# algyan-6th-03.net
KiCad netlist of a schematic drawn in EAGLE
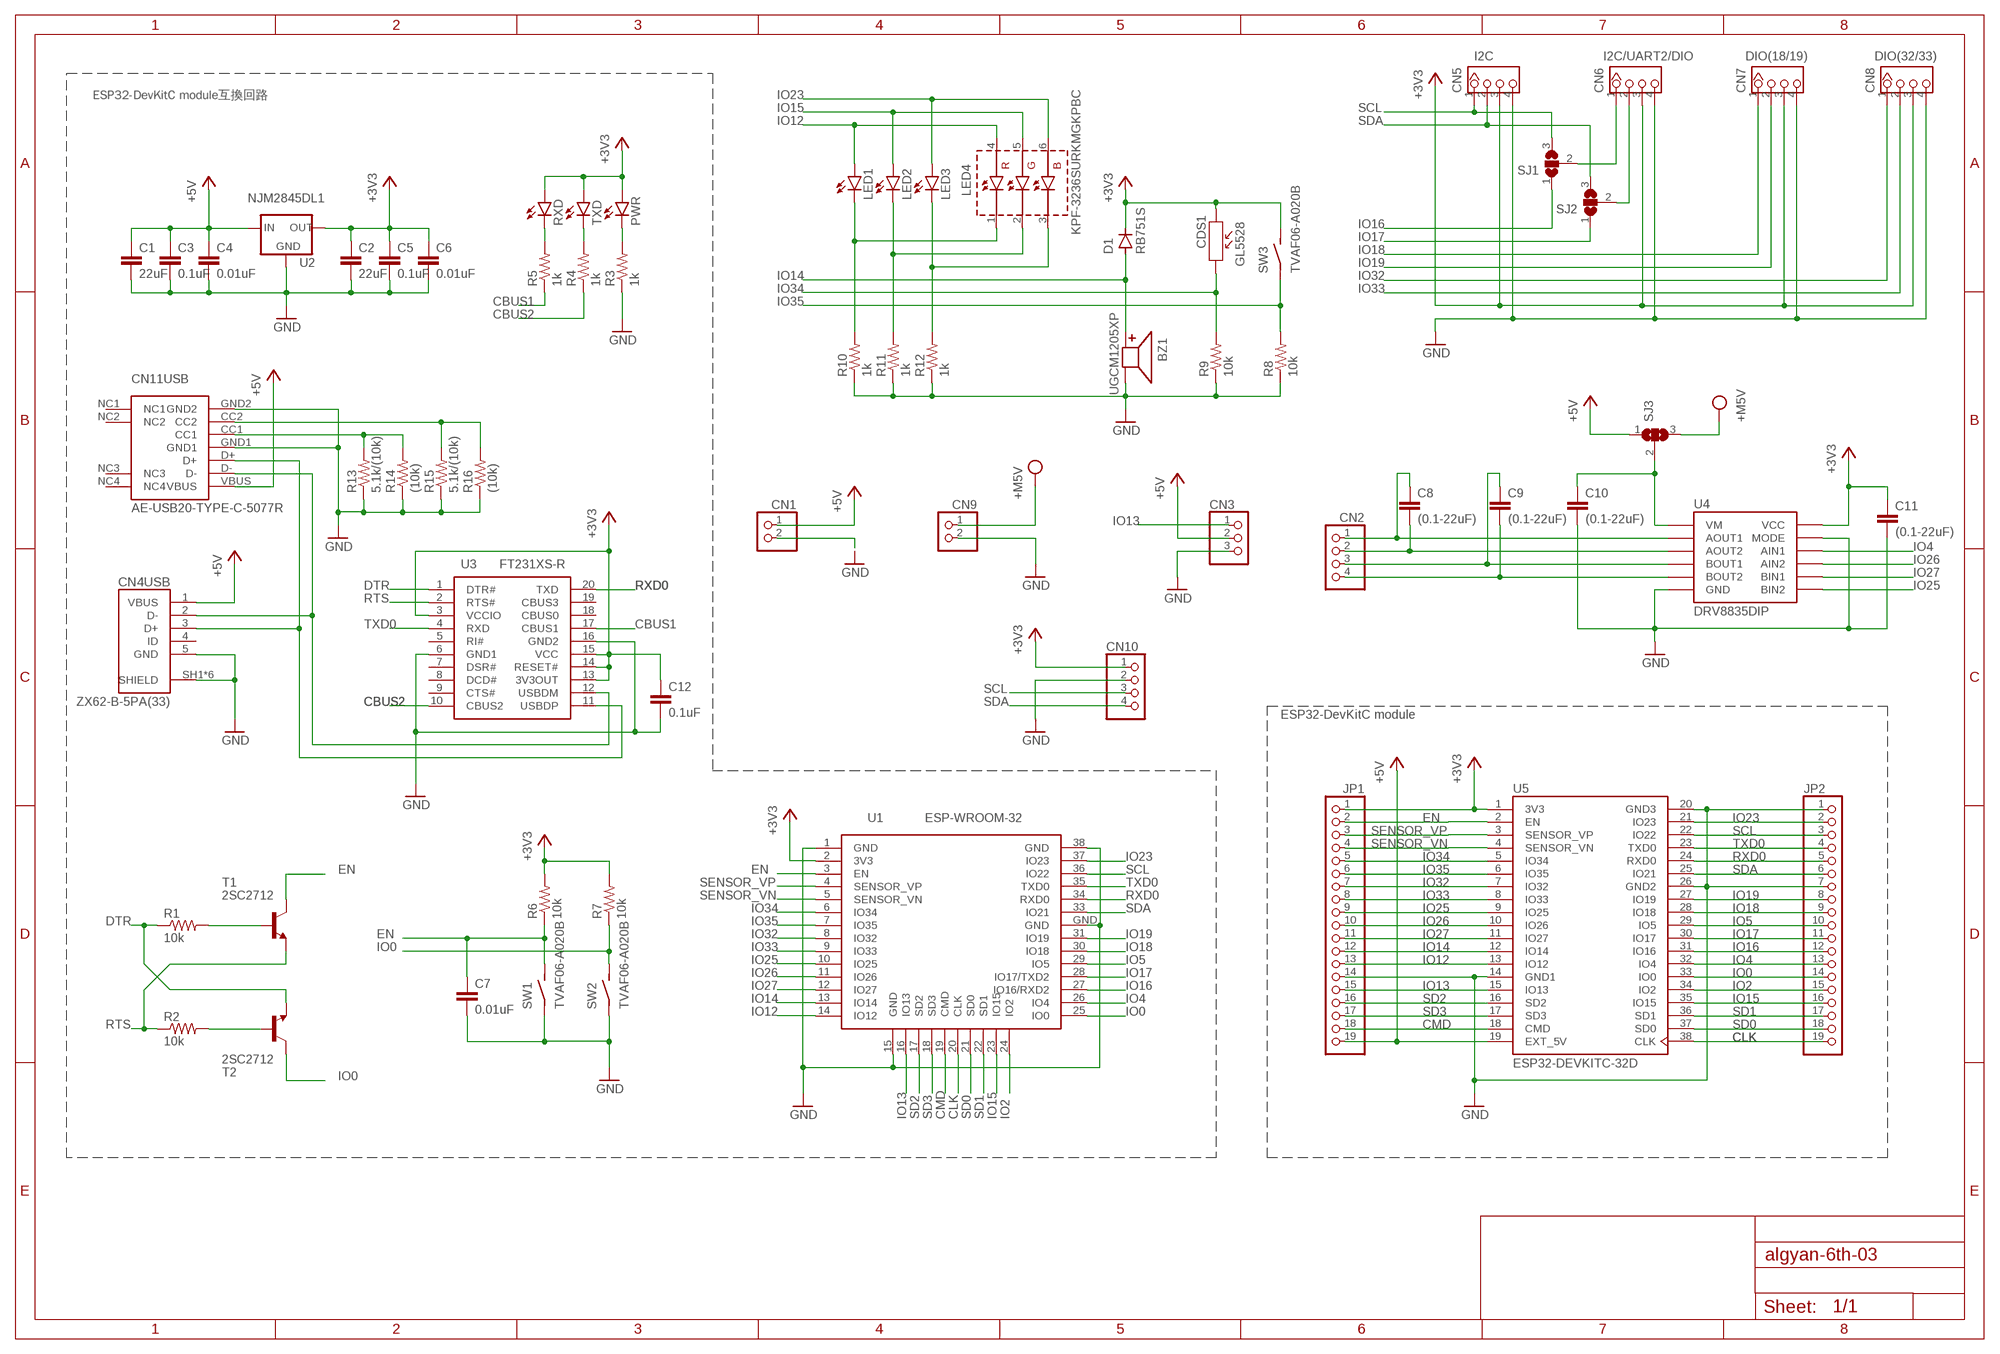
[diagram p0: schematic, sheet 1]

(export (version "E")
  (design (tool "Eeschema 10.0.6"))
  (components
    (comp (ref "BZ1")
      (value "UGCM1205XP")
      (footprint "eagle-import:UGCM1205XP")
      (libsource (lib "eagle-import") (part "UGCM1205XP"))
    )
    (comp (ref "C1")
      (value "22uF")
      (footprint "eagle-import:C3216")
      (libsource (lib "eagle-import") (part "C-EUC3216"))
    )
    (comp (ref "C2")
      (value "22uF")
      (footprint "eagle-import:C3216")
      (libsource (lib "eagle-import") (part "C-EUC3216"))
    )
    (comp (ref "C3")
      (value "0.1uF")
      (footprint "eagle-import:C2012")
      (libsource (lib "eagle-import") (part "C-EUC2012"))
    )
    (comp (ref "C4")
      (value "0.01uF")
      (footprint "eagle-import:C1608")
      (libsource (lib "eagle-import") (part "C-EUC1608"))
    )
    (comp (ref "C5")
      (value "0.1uF")
      (footprint "eagle-import:C2012")
      (libsource (lib "eagle-import") (part "C-EUC2012"))
    )
    (comp (ref "C6")
      (value "0.01uF")
      (footprint "eagle-import:C1608")
      (libsource (lib "eagle-import") (part "C-EUC1608"))
    )
    (comp (ref "C7")
      (value "0.01uF")
      (footprint "eagle-import:C1608")
      (libsource (lib "eagle-import") (part "C-EUC1608"))
    )
    (comp (ref "C8")
      (value "(0.1-22uF)")
      (footprint "eagle-import:C3216")
      (libsource (lib "eagle-import") (part "C-EUC3216"))
    )
    (comp (ref "C9")
      (value "(0.1-22uF)")
      (footprint "eagle-import:C3216")
      (libsource (lib "eagle-import") (part "C-EUC3216"))
    )
    (comp (ref "C10")
      (value "(0.1-22uF)")
      (footprint "eagle-import:C3216")
      (libsource (lib "eagle-import") (part "C-EUC3216"))
    )
    (comp (ref "C11")
      (value "(0.1-22uF)")
      (footprint "eagle-import:C3216")
      (libsource (lib "eagle-import") (part "C-EUC3216"))
    )
    (comp (ref "C12")
      (value "0.1uF")
      (footprint "eagle-import:C2012")
      (libsource (lib "eagle-import") (part "C-EUC2012"))
    )
    (comp (ref "CDS1")
      (value "GL5528")
      (footprint "eagle-import:GL5528")
      (libsource (lib "eagle-import") (part "GL5528"))
    )
    (comp (ref "CN1")
      (value "PINHD-1X2")
      (footprint "eagle-import:1X02")
      (libsource (lib "eagle-import") (part "PINHD-1X2"))
    )
    (comp (ref "CN2")
      (value "PINHD-1X4")
      (footprint "eagle-import:1X04")
      (libsource (lib "eagle-import") (part "PINHD-1X4"))
    )
    (comp (ref "CN3")
      (value "PINHD-1X3")
      (footprint "eagle-import:1X03")
      (libsource (lib "eagle-import") (part "PINHD-1X3"))
    )
    (comp (ref "CN4USB")
      (value "ZX62-B-5PA(33)")
      (footprint "eagle-import:HRS_ZX62-B-5PA(33)")
      (fields (field (name "MF") "Hirose"))
      (libsource (lib "eagle-import") (part "ZX62-B-5PA(33)"))
    )
    (comp (ref "CN5")
      (value "I2C")
      (footprint "eagle-import:HW4-2.0")
      (fields (field (name "CN5") "I2C"))
      (libsource (lib "eagle-import") (part "GROVE-CONNECTOR-DIP(4P-2.0)"))
    )
    (comp (ref "CN6")
      (value "I2C/UART2")
      (footprint "eagle-import:HW4-2.0")
      (fields (field (name "CN6") "I2C/UART2/DIO"))
      (libsource (lib "eagle-import") (part "GROVE-CONNECTOR-DIP(4P-2.0)"))
    )
    (comp (ref "CN7")
      (value "DIO(18/19)")
      (footprint "eagle-import:HW4-2.0")
      (fields (field (name "CN7") "DIO(18/19)"))
      (libsource (lib "eagle-import") (part "GROVE-CONNECTOR-DIP(4P-2.0)"))
    )
    (comp (ref "CN8")
      (value "DIO(32/33)")
      (footprint "eagle-import:HW4-2.0")
      (fields (field (name "CN8") "DIO(32/33)"))
      (libsource (lib "eagle-import") (part "GROVE-CONNECTOR-DIP(4P-2.0)"))
    )
    (comp (ref "CN9")
      (value "PINHD-1X2")
      (footprint "eagle-import:1X02")
      (libsource (lib "eagle-import") (part "PINHD-1X2"))
    )
    (comp (ref "CN10")
      (value "PINHD-1X4/90")
      (footprint "eagle-import:1X04_90")
      (libsource (lib "eagle-import") (part "PINHD-1X4/90"))
    )
    (comp (ref "CN11USB")
      (value "AE-USB20-TYPE-C-5077R")
      (footprint "eagle-import:AE-USB20-TYPE-C-5077R")
      (libsource (lib "eagle-import") (part "AE-USB20-TYPE-C-5077R"))
    )
    (comp (ref "D1")
      (value "RB751S")
      (footprint "eagle-import:SOD-523")
      (libsource (lib "eagle-import") (part "RB751S"))
    )
    (comp (ref "JP1")
      (value "PINHD-1X19")
      (footprint "eagle-import:1X19")
      (libsource (lib "eagle-import") (part "PINHD-1X19"))
    )
    (comp (ref "JP2")
      (value "PINHD-1X19")
      (footprint "eagle-import:1X19")
      (libsource (lib "eagle-import") (part "PINHD-1X19"))
    )
    (comp (ref "LED1")
      (value "LEDCHIPLED_0805")
      (footprint "eagle-import:CHIPLED_0805")
      (libsource (lib "eagle-import") (part "LEDCHIPLED_0805"))
    )
    (comp (ref "LED2")
      (value "LEDCHIPLED_0805")
      (footprint "eagle-import:CHIPLED_0805")
      (libsource (lib "eagle-import") (part "LEDCHIPLED_0805"))
    )
    (comp (ref "LED3")
      (value "LEDCHIPLED_0805")
      (footprint "eagle-import:CHIPLED_0805")
      (libsource (lib "eagle-import") (part "LEDCHIPLED_0805"))
    )
    (comp (ref "LED4")
      (value "KPF-3236SURKMGKPBC")
      (footprint "eagle-import:KPF-3236SURKMGKPBC")
      (libsource (lib "eagle-import") (part "KPF-3236SURKMGKPBC"))
    )
    (comp (ref "PWR")
      (value "LEDCHIPLED_0805")
      (footprint "eagle-import:CHIPLED_0805")
      (libsource (lib "eagle-import") (part "LEDCHIPLED_0805"))
    )
    (comp (ref "R1")
      (value "10k")
      (footprint "eagle-import:R2012")
      (libsource (lib "eagle-import") (part "resistor_348_R-US_R2012"))
    )
    (comp (ref "R2")
      (value "10k")
      (footprint "eagle-import:R2012")
      (libsource (lib "eagle-import") (part "resistor_348_R-US_R2012"))
    )
    (comp (ref "R3")
      (value "1k")
      (footprint "eagle-import:R2012")
      (libsource (lib "eagle-import") (part "R-US_R2012"))
    )
    (comp (ref "R4")
      (value "1k")
      (footprint "eagle-import:R2012")
      (libsource (lib "eagle-import") (part "R-US_R2012"))
    )
    (comp (ref "R5")
      (value "1k")
      (footprint "eagle-import:R2012")
      (libsource (lib "eagle-import") (part "R-US_R2012"))
    )
    (comp (ref "R6")
      (value "10k")
      (footprint "eagle-import:R2012")
      (libsource (lib "eagle-import") (part "resistor_348_R-US_R2012"))
    )
    (comp (ref "R7")
      (value "10k")
      (footprint "eagle-import:R2012")
      (libsource (lib "eagle-import") (part "resistor_348_R-US_R2012"))
    )
    (comp (ref "R8")
      (value "10k")
      (footprint "eagle-import:R2012")
      (libsource (lib "eagle-import") (part "resistor_348_R-US_R2012"))
    )
    (comp (ref "R9")
      (value "10k")
      (footprint "eagle-import:R2012")
      (libsource (lib "eagle-import") (part "resistor_348_R-US_R2012"))
    )
    (comp (ref "R10")
      (value "1k")
      (footprint "eagle-import:R2012")
      (libsource (lib "eagle-import") (part "R-US_R2012"))
    )
    (comp (ref "R11")
      (value "1k")
      (footprint "eagle-import:R2012")
      (libsource (lib "eagle-import") (part "R-US_R2012"))
    )
    (comp (ref "R12")
      (value "1k")
      (footprint "eagle-import:R2012")
      (libsource (lib "eagle-import") (part "R-US_R2012"))
    )
    (comp (ref "R13")
      (value "5.1k/(10k)")
      (footprint "eagle-import:R2012")
      (libsource (lib "eagle-import") (part "resistor_348_R-US_R2012"))
    )
    (comp (ref "R14")
      (value "(10k)")
      (footprint "eagle-import:R2012")
      (libsource (lib "eagle-import") (part "resistor_348_R-US_R2012"))
    )
    (comp (ref "R15")
      (value "5.1k/(10k)")
      (footprint "eagle-import:R2012")
      (libsource (lib "eagle-import") (part "resistor_348_R-US_R2012"))
    )
    (comp (ref "R16")
      (value "(10k)")
      (footprint "eagle-import:R2012")
      (libsource (lib "eagle-import") (part "resistor_348_R-US_R2012"))
    )
    (comp (ref "RXD")
      (value "LEDCHIPLED_0805")
      (footprint "eagle-import:CHIPLED_0805")
      (libsource (lib "eagle-import") (part "LEDCHIPLED_0805"))
    )
    (comp (ref "SJ1")
      (value "SJ2W")
      (footprint "eagle-import:SJ_2")
      (libsource (lib "eagle-import") (part "SJ2W"))
    )
    (comp (ref "SJ2")
      (value "SJ2W")
      (footprint "eagle-import:SJ_2")
      (libsource (lib "eagle-import") (part "SJ2W"))
    )
    (comp (ref "SJ3")
      (value "SJ2W")
      (footprint "eagle-import:SJ_2")
      (libsource (lib "eagle-import") (part "SJ2W"))
    )
    (comp (ref "SW1")
      (value "TVAF06-A020B")
      (footprint "eagle-import:TVAF06-A020B")
      (libsource (lib "eagle-import") (part "TVAF06-A020B"))
    )
    (comp (ref "SW2")
      (value "TVAF06-A020B")
      (footprint "eagle-import:TVAF06-A020B")
      (libsource (lib "eagle-import") (part "TVAF06-A020B"))
    )
    (comp (ref "SW3")
      (value "TVAF06-A020B")
      (footprint "eagle-import:TVAF06-A020B")
      (libsource (lib "eagle-import") (part "TVAF06-A020B"))
    )
    (comp (ref "T1")
      (value "2SC2712")
      (footprint "eagle-import:SOT23-BEC")
      (libsource (lib "eagle-import") (part "2SC2712YSOT23-BECBC808"))
    )
    (comp (ref "T2")
      (value "2SC2712")
      (footprint "eagle-import:SOT23-BEC")
      (libsource (lib "eagle-import") (part "2SC2712YSOT23-BECBC808"))
    )
    (comp (ref "TXD")
      (value "LEDCHIPLED_0805")
      (footprint "eagle-import:CHIPLED_0805")
      (libsource (lib "eagle-import") (part "LEDCHIPLED_0805"))
    )
    (comp (ref "U1")
      (value "ESP-WROOM-32")
      (footprint "eagle-import:ESP-WROOM-32")
      (libsource (lib "eagle-import") (part "ESP-WROOM-32"))
    )
    (comp (ref "U2")
      (value "NJM2845DL1")
      (footprint "eagle-import:D-PAK_TO252AA")
      (libsource (lib "eagle-import") (part "NJM2845DL1"))
    )
    (comp (ref "U3")
      (value "FT231XS-R")
      (footprint "eagle-import:SOP64P599X175-20N")
      (fields (field (name "RS_PART_NUMBER") "7570032P"))
      (libsource (lib "eagle-import") (part "FT231XS-R"))
    )
    (comp (ref "U4")
      (value "DRV8835DIP")
      (footprint "eagle-import:DRV8835DIP")
      (libsource (lib "eagle-import") (part "DRV8835DIP"))
    )
    (comp (ref "U5")
      (value "ESP32-DEVKITC-32D")
      (footprint "eagle-import:MODULE_ESP32-DEVKITC-32D")
      (fields (field (name "MF") "Espressif Systems"))
      (libsource (lib "eagle-import") (part "ESP32-DEVKITC-32D"))
    )
  )
  (nets
    (net (code "1") (name "+3V3") (class "Default")
      (node (ref "C11") (pin "1") (pinfunction "1_1") (pintype "passive"))
      (node (ref "C12") (pin "1") (pinfunction "1_1") (pintype "passive"))
      (node (ref "C2") (pin "1") (pinfunction "1_1") (pintype "passive"))
      (node (ref "C5") (pin "1") (pinfunction "1_1") (pintype "passive"))
      (node (ref "C6") (pin "1") (pinfunction "1_1") (pintype "passive"))
      (node (ref "CDS1") (pin "1") (pinfunction "P$1_1") (pintype "bidirectional"))
      (node (ref "CN10") (pin "1") (pinfunction "1_1") (pintype "passive"))
      (node (ref "CN5") (pin "3") (pinfunction "3_3") (pintype "bidirectional"))
      (node (ref "CN6") (pin "3") (pinfunction "3_3") (pintype "bidirectional"))
      (node (ref "CN7") (pin "3") (pinfunction "3_3") (pintype "bidirectional"))
      (node (ref "CN8") (pin "3") (pinfunction "3_3") (pintype "bidirectional"))
      (node (ref "D1") (pin "C") (pinfunction "C_C") (pintype "passive"))
      (node (ref "JP1") (pin "1") (pinfunction "1_1") (pintype "passive"))
      (node (ref "PWR") (pin "A") (pinfunction "A_A") (pintype "passive"))
      (node (ref "R6") (pin "2") (pinfunction "2_2") (pintype "passive"))
      (node (ref "R7") (pin "2") (pinfunction "2_2") (pintype "passive"))
      (node (ref "RXD") (pin "A") (pinfunction "A_A") (pintype "passive"))
      (node (ref "SW3") (pin "2") (pinfunction "S_2") (pintype "passive"))
      (node (ref "TXD") (pin "A") (pinfunction "A_A") (pintype "passive"))
      (node (ref "U1") (pin "2") (pinfunction "3V3_2") (pintype "power_in"))
      (node (ref "U2") (pin "3") (pinfunction "OUT_3") (pintype "passive"))
      (node (ref "U3") (pin "13") (pinfunction "3V3OUT_13") (pintype "output"))
      (node (ref "U3") (pin "14") (pinfunction "RESET#_14") (pintype "bidirectional"))
      (node (ref "U3") (pin "15") (pinfunction "VCC_15") (pintype "power_in"))
      (node (ref "U3") (pin "3") (pinfunction "VCCIO_3") (pintype "power_in"))
      (node (ref "U4") (pin "VCC") (pinfunction "VCC_VCC") (pintype "bidirectional"))
      (node (ref "U5") (pin "1") (pinfunction "3V3_1") (pintype "power_in"))
    )
    (net (code "2") (name "+5V") (class "Default")
      (node (ref "C1") (pin "1") (pinfunction "1_1") (pintype "passive"))
      (node (ref "C3") (pin "1") (pinfunction "1_1") (pintype "passive"))
      (node (ref "C4") (pin "1") (pinfunction "1_1") (pintype "passive"))
      (node (ref "CN1") (pin "1") (pinfunction "1_1") (pintype "passive"))
      (node (ref "CN11USB") (pin "VBUS") (pinfunction "VBUS_VBUS") (pintype "bidirectional"))
      (node (ref "CN3") (pin "2") (pinfunction "2_2") (pintype "passive"))
      (node (ref "CN4USB") (pin "1") (pinfunction "VBUS_1") (pintype "passive"))
      (node (ref "JP1") (pin "19") (pinfunction "19_19") (pintype "passive"))
      (node (ref "SJ3") (pin "1") (pinfunction "1_1") (pintype "passive"))
      (node (ref "U2") (pin "1") (pinfunction "IN_1") (pintype "input"))
      (node (ref "U5") (pin "19") (pinfunction "EXT_5V_19") (pintype "power_in"))
    )
    (net (code "3") (name "+M5V") (class "Default")
      (node (ref "CN9") (pin "1") (pinfunction "1_1") (pintype "passive"))
      (node (ref "SJ3") (pin "3") (pinfunction "3_3") (pintype "passive"))
    )
    (net (code "4") (name "/CBUS1") (class "Default")
      (node (ref "R5") (pin "1") (pinfunction "1_1") (pintype "passive"))
      (node (ref "U3") (pin "17") (pinfunction "CBUS1_17") (pintype "bidirectional"))
    )
    (net (code "5") (name "/CBUS2") (class "Default")
      (node (ref "R4") (pin "1") (pinfunction "1_1") (pintype "passive"))
      (node (ref "U3") (pin "10") (pinfunction "CBUS2_10") (pintype "bidirectional"))
    )
    (net (code "6") (name "/CLK") (class "Default")
      (node (ref "JP2") (pin "19") (pinfunction "19_19") (pintype "passive"))
      (node (ref "U1") (pin "20") (pinfunction "CLK_20") (pintype "bidirectional"))
      (node (ref "U5") (pin "38") (pinfunction "CLK_38") (pintype "input"))
    )
    (net (code "7") (name "/CMD") (class "Default")
      (node (ref "JP1") (pin "18") (pinfunction "18_18") (pintype "passive"))
      (node (ref "U1") (pin "19") (pinfunction "CMD_19") (pintype "bidirectional"))
      (node (ref "U5") (pin "18") (pinfunction "CMD_18") (pintype "bidirectional"))
    )
    (net (code "8") (name "/DTR") (class "Default")
      (node (ref "R1") (pin "1") (pinfunction "1_1") (pintype "passive"))
      (node (ref "T2") (pin "E") (pinfunction "E_E") (pintype "passive"))
      (node (ref "U3") (pin "1") (pinfunction "DTR#_1") (pintype "bidirectional"))
    )
    (net (code "9") (name "/EN") (class "Default")
      (node (ref "C7") (pin "1") (pinfunction "1_1") (pintype "passive"))
      (node (ref "JP1") (pin "2") (pinfunction "2_2") (pintype "passive"))
      (node (ref "R6") (pin "1") (pinfunction "1_1") (pintype "passive"))
      (node (ref "SW1") (pin "2") (pinfunction "S_2") (pintype "passive"))
      (node (ref "T1") (pin "C") (pinfunction "C_C") (pintype "passive"))
      (node (ref "U1") (pin "3") (pinfunction "EN_3") (pintype "input"))
      (node (ref "U5") (pin "2") (pinfunction "EN_2") (pintype "input"))
    )
    (net (code "10") (name "/IO0") (class "Default")
      (node (ref "JP2") (pin "14") (pinfunction "14_14") (pintype "passive"))
      (node (ref "R7") (pin "1") (pinfunction "1_1") (pintype "passive"))
      (node (ref "SW2") (pin "2") (pinfunction "S_2") (pintype "passive"))
      (node (ref "T2") (pin "C") (pinfunction "C_C") (pintype "passive"))
      (node (ref "U1") (pin "25") (pinfunction "IO0_25") (pintype "bidirectional"))
      (node (ref "U5") (pin "33") (pinfunction "IO0_33") (pintype "bidirectional"))
    )
    (net (code "11") (name "/IO2") (class "Default")
      (node (ref "JP2") (pin "15") (pinfunction "15_15") (pintype "passive"))
      (node (ref "U1") (pin "24") (pinfunction "IO2_24") (pintype "bidirectional"))
      (node (ref "U5") (pin "34") (pinfunction "IO2_34") (pintype "bidirectional"))
    )
    (net (code "12") (name "/IO4") (class "Default")
      (node (ref "JP2") (pin "13") (pinfunction "13_13") (pintype "passive"))
      (node (ref "U1") (pin "26") (pinfunction "IO4_26") (pintype "bidirectional"))
      (node (ref "U4") (pin "AIN1") (pinfunction "AIN1_AIN1") (pintype "bidirectional"))
      (node (ref "U5") (pin "32") (pinfunction "IO4_32") (pintype "bidirectional"))
    )
    (net (code "13") (name "/IO5") (class "Default")
      (node (ref "JP2") (pin "10") (pinfunction "10_10") (pintype "passive"))
      (node (ref "U1") (pin "29") (pinfunction "IO5_29") (pintype "bidirectional"))
      (node (ref "U5") (pin "29") (pinfunction "IO5_29") (pintype "bidirectional"))
    )
    (net (code "14") (name "/IO12") (class "Default")
      (node (ref "JP1") (pin "13") (pinfunction "13_13") (pintype "passive"))
      (node (ref "LED1") (pin "A") (pinfunction "A_A") (pintype "passive"))
      (node (ref "LED4") (pin "4") (pinfunction "RA_4") (pintype "passive"))
      (node (ref "U1") (pin "14") (pinfunction "IO12_14") (pintype "bidirectional"))
      (node (ref "U5") (pin "13") (pinfunction "IO12_13") (pintype "bidirectional"))
    )
    (net (code "15") (name "/IO13") (class "Default")
      (node (ref "CN3") (pin "1") (pinfunction "1_1") (pintype "passive"))
      (node (ref "JP1") (pin "15") (pinfunction "15_15") (pintype "passive"))
      (node (ref "U1") (pin "16") (pinfunction "IO13_16") (pintype "bidirectional"))
      (node (ref "U5") (pin "15") (pinfunction "IO13_15") (pintype "bidirectional"))
    )
    (net (code "16") (name "/IO14") (class "Default")
      (node (ref "BZ1") (pin "P$1") (pinfunction "1_P$1") (pintype "passive"))
      (node (ref "D1") (pin "A") (pinfunction "A_A") (pintype "passive"))
      (node (ref "JP1") (pin "12") (pinfunction "12_12") (pintype "passive"))
      (node (ref "U1") (pin "13") (pinfunction "IO14_13") (pintype "bidirectional"))
      (node (ref "U5") (pin "12") (pinfunction "IO14_12") (pintype "bidirectional"))
    )
    (net (code "17") (name "/IO15") (class "Default")
      (node (ref "JP2") (pin "16") (pinfunction "16_16") (pintype "passive"))
      (node (ref "LED2") (pin "A") (pinfunction "A_A") (pintype "passive"))
      (node (ref "LED4") (pin "5") (pinfunction "GA_5") (pintype "passive"))
      (node (ref "U1") (pin "23") (pinfunction "IO15_23") (pintype "bidirectional"))
      (node (ref "U5") (pin "35") (pinfunction "IO15_35") (pintype "bidirectional"))
    )
    (net (code "18") (name "/IO16") (class "Default")
      (node (ref "JP2") (pin "12") (pinfunction "12_12") (pintype "passive"))
      (node (ref "SJ1") (pin "1") (pinfunction "1_1") (pintype "passive"))
      (node (ref "U1") (pin "27") (pinfunction "IO16/RXD2_27") (pintype "bidirectional"))
      (node (ref "U5") (pin "31") (pinfunction "IO16_31") (pintype "bidirectional"))
    )
    (net (code "19") (name "/IO17") (class "Default")
      (node (ref "JP2") (pin "11") (pinfunction "11_11") (pintype "passive"))
      (node (ref "SJ2") (pin "1") (pinfunction "1_1") (pintype "passive"))
      (node (ref "U1") (pin "28") (pinfunction "IO17/TXD2_28") (pintype "bidirectional"))
      (node (ref "U5") (pin "30") (pinfunction "IO17_30") (pintype "bidirectional"))
    )
    (net (code "20") (name "/IO18") (class "Default")
      (node (ref "CN7") (pin "1") (pinfunction "1_1") (pintype "bidirectional"))
      (node (ref "JP2") (pin "9") (pinfunction "9_9") (pintype "passive"))
      (node (ref "U1") (pin "30") (pinfunction "IO18_30") (pintype "bidirectional"))
      (node (ref "U5") (pin "28") (pinfunction "IO18_28") (pintype "bidirectional"))
    )
    (net (code "21") (name "/IO19") (class "Default")
      (node (ref "CN7") (pin "2") (pinfunction "2_2") (pintype "bidirectional"))
      (node (ref "JP2") (pin "8") (pinfunction "8_8") (pintype "passive"))
      (node (ref "U1") (pin "31") (pinfunction "IO19_31") (pintype "bidirectional"))
      (node (ref "U5") (pin "27") (pinfunction "IO19_27") (pintype "bidirectional"))
    )
    (net (code "22") (name "/IO23") (class "Default")
      (node (ref "JP2") (pin "2") (pinfunction "2_2") (pintype "passive"))
      (node (ref "LED3") (pin "A") (pinfunction "A_A") (pintype "passive"))
      (node (ref "LED4") (pin "6") (pinfunction "BA_6") (pintype "passive"))
      (node (ref "U1") (pin "37") (pinfunction "IO23_37") (pintype "bidirectional"))
      (node (ref "U5") (pin "21") (pinfunction "IO23_21") (pintype "bidirectional"))
    )
    (net (code "23") (name "/IO25") (class "Default")
      (node (ref "JP1") (pin "9") (pinfunction "9_9") (pintype "passive"))
      (node (ref "U1") (pin "10") (pinfunction "IO25_10") (pintype "bidirectional"))
      (node (ref "U4") (pin "BIN2") (pinfunction "BIN2_BIN2") (pintype "bidirectional"))
      (node (ref "U5") (pin "9") (pinfunction "IO25_9") (pintype "bidirectional"))
    )
    (net (code "24") (name "/IO26") (class "Default")
      (node (ref "JP1") (pin "10") (pinfunction "10_10") (pintype "passive"))
      (node (ref "U1") (pin "11") (pinfunction "IO26_11") (pintype "bidirectional"))
      (node (ref "U4") (pin "AIN2") (pinfunction "AIN2_AIN2") (pintype "bidirectional"))
      (node (ref "U5") (pin "10") (pinfunction "IO26_10") (pintype "bidirectional"))
    )
    (net (code "25") (name "/IO27") (class "Default")
      (node (ref "JP1") (pin "11") (pinfunction "11_11") (pintype "passive"))
      (node (ref "U1") (pin "12") (pinfunction "IO27_12") (pintype "bidirectional"))
      (node (ref "U4") (pin "BIN1") (pinfunction "BIN1_BIN1") (pintype "bidirectional"))
      (node (ref "U5") (pin "11") (pinfunction "IO27_11") (pintype "bidirectional"))
    )
    (net (code "26") (name "/IO32") (class "Default")
      (node (ref "CN8") (pin "1") (pinfunction "1_1") (pintype "bidirectional"))
      (node (ref "JP1") (pin "7") (pinfunction "7_7") (pintype "passive"))
      (node (ref "U1") (pin "8") (pinfunction "IO32_8") (pintype "bidirectional"))
      (node (ref "U5") (pin "7") (pinfunction "IO32_7") (pintype "bidirectional"))
    )
    (net (code "27") (name "/IO33") (class "Default")
      (node (ref "CN8") (pin "2") (pinfunction "2_2") (pintype "bidirectional"))
      (node (ref "JP1") (pin "8") (pinfunction "8_8") (pintype "passive"))
      (node (ref "U1") (pin "9") (pinfunction "IO33_9") (pintype "bidirectional"))
      (node (ref "U5") (pin "8") (pinfunction "IO33_8") (pintype "bidirectional"))
    )
    (net (code "28") (name "/IO34") (class "Default")
      (node (ref "CDS1") (pin "2") (pinfunction "P$2_2") (pintype "bidirectional"))
      (node (ref "JP1") (pin "5") (pinfunction "5_5") (pintype "passive"))
      (node (ref "R9") (pin "2") (pinfunction "2_2") (pintype "passive"))
      (node (ref "U1") (pin "6") (pinfunction "IO34_6") (pintype "bidirectional"))
      (node (ref "U5") (pin "5") (pinfunction "IO34_5") (pintype "bidirectional"))
    )
    (net (code "29") (name "/IO35") (class "Default")
      (node (ref "JP1") (pin "6") (pinfunction "6_6") (pintype "passive"))
      (node (ref "R8") (pin "2") (pinfunction "2_2") (pintype "passive"))
      (node (ref "SW3") (pin "1") (pinfunction "P_1") (pintype "passive"))
      (node (ref "U1") (pin "7") (pinfunction "IO35_7") (pintype "bidirectional"))
      (node (ref "U5") (pin "6") (pinfunction "IO35_6") (pintype "bidirectional"))
    )
    (net (code "30") (name "/RTS") (class "Default")
      (node (ref "R2") (pin "1") (pinfunction "1_1") (pintype "passive"))
      (node (ref "T1") (pin "E") (pinfunction "E_E") (pintype "passive"))
      (node (ref "U3") (pin "2") (pinfunction "RTS#_2") (pintype "bidirectional"))
    )
    (net (code "31") (name "/RXD0") (class "Default")
      (node (ref "JP2") (pin "5") (pinfunction "5_5") (pintype "passive"))
      (node (ref "U1") (pin "34") (pinfunction "RXD0_34") (pintype "bidirectional"))
      (node (ref "U3") (pin "20") (pinfunction "TXD_20") (pintype "bidirectional"))
      (node (ref "U5") (pin "24") (pinfunction "RXD0_24") (pintype "input"))
    )
    (net (code "32") (name "/SCL") (class "Default")
      (node (ref "CN10") (pin "3") (pinfunction "3_3") (pintype "passive"))
      (node (ref "CN5") (pin "1") (pinfunction "1_1") (pintype "bidirectional"))
      (node (ref "JP2") (pin "3") (pinfunction "3_3") (pintype "passive"))
      (node (ref "SJ1") (pin "3") (pinfunction "3_3") (pintype "passive"))
      (node (ref "U1") (pin "36") (pinfunction "IO22_36") (pintype "bidirectional"))
      (node (ref "U5") (pin "22") (pinfunction "IO22_22") (pintype "bidirectional"))
    )
    (net (code "33") (name "/SD0") (class "Default")
      (node (ref "JP2") (pin "18") (pinfunction "18_18") (pintype "passive"))
      (node (ref "U1") (pin "21") (pinfunction "SD0_21") (pintype "bidirectional"))
      (node (ref "U5") (pin "37") (pinfunction "SD0_37") (pintype "bidirectional"))
    )
    (net (code "34") (name "/SD1") (class "Default")
      (node (ref "JP2") (pin "17") (pinfunction "17_17") (pintype "passive"))
      (node (ref "U1") (pin "22") (pinfunction "SD1_22") (pintype "bidirectional"))
      (node (ref "U5") (pin "36") (pinfunction "SD1_36") (pintype "bidirectional"))
    )
    (net (code "35") (name "/SD2") (class "Default")
      (node (ref "JP1") (pin "16") (pinfunction "16_16") (pintype "passive"))
      (node (ref "U1") (pin "17") (pinfunction "SD2_17") (pintype "bidirectional"))
      (node (ref "U5") (pin "16") (pinfunction "SD2_16") (pintype "bidirectional"))
    )
    (net (code "36") (name "/SD3") (class "Default")
      (node (ref "JP1") (pin "17") (pinfunction "17_17") (pintype "passive"))
      (node (ref "U1") (pin "18") (pinfunction "SD3_18") (pintype "bidirectional"))
      (node (ref "U5") (pin "17") (pinfunction "SD3_17") (pintype "bidirectional"))
    )
    (net (code "37") (name "/SDA") (class "Default")
      (node (ref "CN10") (pin "4") (pinfunction "4_4") (pintype "passive"))
      (node (ref "CN5") (pin "2") (pinfunction "2_2") (pintype "bidirectional"))
      (node (ref "JP2") (pin "6") (pinfunction "6_6") (pintype "passive"))
      (node (ref "SJ2") (pin "3") (pinfunction "3_3") (pintype "passive"))
      (node (ref "U1") (pin "33") (pinfunction "IO21_33") (pintype "bidirectional"))
      (node (ref "U5") (pin "25") (pinfunction "IO21_25") (pintype "bidirectional"))
    )
    (net (code "38") (name "/SENSOR_VN") (class "Default")
      (node (ref "JP1") (pin "4") (pinfunction "4_4") (pintype "passive"))
      (node (ref "U1") (pin "5") (pinfunction "SENSOR_VN_5") (pintype "bidirectional"))
      (node (ref "U5") (pin "4") (pinfunction "SENSOR_VN_4") (pintype "input"))
    )
    (net (code "39") (name "/SENSOR_VP") (class "Default")
      (node (ref "JP1") (pin "3") (pinfunction "3_3") (pintype "passive"))
      (node (ref "U1") (pin "4") (pinfunction "SENSOR_VP_4") (pintype "bidirectional"))
      (node (ref "U5") (pin "3") (pinfunction "SENSOR_VP_3") (pintype "input"))
    )
    (net (code "40") (name "/TXD0") (class "Default")
      (node (ref "JP2") (pin "4") (pinfunction "4_4") (pintype "passive"))
      (node (ref "U1") (pin "35") (pinfunction "TXD0_35") (pintype "bidirectional"))
      (node (ref "U3") (pin "4") (pinfunction "RXD_4") (pintype "bidirectional"))
      (node (ref "U5") (pin "23") (pinfunction "TXD0_23") (pintype "output"))
    )
    (net (code "41") (name "GND") (class "Default")
      (node (ref "BZ1") (pin "P$2") (pinfunction "2_P$2") (pintype "passive"))
      (node (ref "C1") (pin "2") (pinfunction "2_2") (pintype "passive"))
      (node (ref "C10") (pin "2") (pinfunction "2_2") (pintype "passive"))
      (node (ref "C11") (pin "2") (pinfunction "2_2") (pintype "passive"))
      (node (ref "C12") (pin "2") (pinfunction "2_2") (pintype "passive"))
      (node (ref "C2") (pin "2") (pinfunction "2_2") (pintype "passive"))
      (node (ref "C3") (pin "2") (pinfunction "2_2") (pintype "passive"))
      (node (ref "C4") (pin "2") (pinfunction "2_2") (pintype "passive"))
      (node (ref "C5") (pin "2") (pinfunction "2_2") (pintype "passive"))
      (node (ref "C6") (pin "2") (pinfunction "2_2") (pintype "passive"))
      (node (ref "C7") (pin "2") (pinfunction "2_2") (pintype "passive"))
      (node (ref "CN1") (pin "2") (pinfunction "2_2") (pintype "passive"))
      (node (ref "CN10") (pin "2") (pinfunction "2_2") (pintype "passive"))
      (node (ref "CN11USB") (pin "GND1") (pinfunction "GND1_GND1") (pintype "bidirectional"))
      (node (ref "CN11USB") (pin "GND2") (pinfunction "GND2_GND2") (pintype "bidirectional"))
      (node (ref "CN3") (pin "3") (pinfunction "3_3") (pintype "passive"))
      (node (ref "CN4USB") (pin "5") (pinfunction "GND_5") (pintype "passive"))
      (node (ref "CN4USB") (pin "SH1") (pinfunction "SHIELD_SH1") (pintype "passive"))
      (node (ref "CN4USB") (pin "SH2") (pinfunction "SHIELD_SH2") (pintype "passive"))
      (node (ref "CN4USB") (pin "SH3") (pinfunction "SHIELD_SH3") (pintype "passive"))
      (node (ref "CN4USB") (pin "SH4") (pinfunction "SHIELD_SH4") (pintype "passive"))
      (node (ref "CN4USB") (pin "SH5") (pinfunction "SHIELD_SH5") (pintype "passive"))
      (node (ref "CN4USB") (pin "SH6") (pinfunction "SHIELD_SH6") (pintype "passive"))
      (node (ref "CN5") (pin "4") (pinfunction "4_4") (pintype "bidirectional"))
      (node (ref "CN6") (pin "4") (pinfunction "4_4") (pintype "bidirectional"))
      (node (ref "CN7") (pin "4") (pinfunction "4_4") (pintype "bidirectional"))
      (node (ref "CN8") (pin "4") (pinfunction "4_4") (pintype "bidirectional"))
      (node (ref "CN9") (pin "2") (pinfunction "2_2") (pintype "passive"))
      (node (ref "JP1") (pin "14") (pinfunction "14_14") (pintype "passive"))
      (node (ref "JP2") (pin "1") (pinfunction "1_1") (pintype "passive"))
      (node (ref "JP2") (pin "7") (pinfunction "7_7") (pintype "passive"))
      (node (ref "R10") (pin "1") (pinfunction "1_1") (pintype "passive"))
      (node (ref "R11") (pin "1") (pinfunction "1_1") (pintype "passive"))
      (node (ref "R12") (pin "1") (pinfunction "1_1") (pintype "passive"))
      (node (ref "R13") (pin "1") (pinfunction "1_1") (pintype "passive"))
      (node (ref "R14") (pin "1") (pinfunction "1_1") (pintype "passive"))
      (node (ref "R15") (pin "1") (pinfunction "1_1") (pintype "passive"))
      (node (ref "R16") (pin "1") (pinfunction "1_1") (pintype "passive"))
      (node (ref "R3") (pin "1") (pinfunction "1_1") (pintype "passive"))
      (node (ref "R8") (pin "1") (pinfunction "1_1") (pintype "passive"))
      (node (ref "R9") (pin "1") (pinfunction "1_1") (pintype "passive"))
      (node (ref "SW1") (pin "1") (pinfunction "P_1") (pintype "passive"))
      (node (ref "SW2") (pin "1") (pinfunction "P_1") (pintype "passive"))
      (node (ref "U1") (pin "1") (pinfunction "GND_1") (pintype "power_in"))
      (node (ref "U1") (pin "15") (pinfunction "GND_15") (pintype "power_in"))
      (node (ref "U1") (pin "38") (pinfunction "GND_38") (pintype "power_in"))
      (node (ref "U1") (pin "GND") (pinfunction "GND_GND") (pintype "power_in"))
      (node (ref "U2") (pin "4") (pinfunction "GND_4") (pintype "input"))
      (node (ref "U3") (pin "16") (pinfunction "GND2_16") (pintype "power_in"))
      (node (ref "U3") (pin "6") (pinfunction "GND1_6") (pintype "power_in"))
      (node (ref "U4") (pin "GND") (pinfunction "GND_GND") (pintype "bidirectional"))
      (node (ref "U4") (pin "MODE") (pinfunction "MODE_MODE") (pintype "bidirectional"))
      (node (ref "U5") (pin "14") (pinfunction "GND1_14") (pintype "power_in"))
      (node (ref "U5") (pin "20") (pinfunction "GND3_20") (pintype "power_in"))
      (node (ref "U5") (pin "26") (pinfunction "GND2_26") (pintype "power_in"))
    )
    (net (code "42") (name "Net-(C8-Pad1)") (class "Default")
      (node (ref "C8") (pin "1") (pinfunction "1_1") (pintype "passive"))
      (node (ref "CN2") (pin "1") (pinfunction "1_1") (pintype "passive"))
      (node (ref "U4") (pin "AOUT1") (pinfunction "AOUT1_AOUT1") (pintype "bidirectional"))
    )
    (net (code "43") (name "Net-(C8-Pad2)") (class "Default")
      (node (ref "C8") (pin "2") (pinfunction "2_2") (pintype "passive"))
      (node (ref "CN2") (pin "2") (pinfunction "2_2") (pintype "passive"))
      (node (ref "U4") (pin "AOUT2") (pinfunction "AOUT2_AOUT2") (pintype "bidirectional"))
    )
    (net (code "44") (name "Net-(C9-Pad1)") (class "Default")
      (node (ref "C9") (pin "1") (pinfunction "1_1") (pintype "passive"))
      (node (ref "CN2") (pin "3") (pinfunction "3_3") (pintype "passive"))
      (node (ref "U4") (pin "BOUT1") (pinfunction "BOUT1_BOUT1") (pintype "bidirectional"))
    )
    (net (code "45") (name "Net-(C9-Pad2)") (class "Default")
      (node (ref "C9") (pin "2") (pinfunction "2_2") (pintype "passive"))
      (node (ref "CN2") (pin "4") (pinfunction "4_4") (pintype "passive"))
      (node (ref "U4") (pin "BOUT2") (pinfunction "BOUT2_BOUT2") (pintype "bidirectional"))
    )
    (net (code "46") (name "Net-(C10-Pad1)") (class "Default")
      (node (ref "C10") (pin "1") (pinfunction "1_1") (pintype "passive"))
      (node (ref "SJ3") (pin "2") (pinfunction "2_2") (pintype "passive"))
      (node (ref "U4") (pin "VM") (pinfunction "VM_VM") (pintype "bidirectional"))
    )
    (net (code "47") (name "Net-(CN4USB-D+)") (class "Default")
      (node (ref "CN11USB") (pin "D+") (pinfunction "D+_D+") (pintype "bidirectional"))
      (node (ref "CN4USB") (pin "3") (pinfunction "D+_3") (pintype "passive"))
      (node (ref "U3") (pin "11") (pinfunction "USBDP_11") (pintype "bidirectional"))
    )
    (net (code "48") (name "Net-(CN4USB-D-)") (class "Default")
      (node (ref "CN11USB") (pin "D-") (pinfunction "D-_D-") (pintype "bidirectional"))
      (node (ref "CN4USB") (pin "2") (pinfunction "D-_2") (pintype "passive"))
      (node (ref "U3") (pin "12") (pinfunction "USBDM_12") (pintype "bidirectional"))
    )
    (net (code "49") (name "Net-(CN6-Pad1)") (class "Default")
      (node (ref "CN6") (pin "1") (pinfunction "1_1") (pintype "bidirectional"))
      (node (ref "SJ1") (pin "2") (pinfunction "2_2") (pintype "passive"))
    )
    (net (code "50") (name "Net-(CN6-Pad2)") (class "Default")
      (node (ref "CN6") (pin "2") (pinfunction "2_2") (pintype "bidirectional"))
      (node (ref "SJ2") (pin "2") (pinfunction "2_2") (pintype "passive"))
    )
    (net (code "51") (name "Net-(CN11USB-PadCC1)") (class "Default")
      (node (ref "CN11USB") (pin "CC1") (pinfunction "CC1_CC1") (pintype "bidirectional"))
      (node (ref "R13") (pin "2") (pinfunction "2_2") (pintype "passive"))
      (node (ref "R14") (pin "2") (pinfunction "2_2") (pintype "passive"))
    )
    (net (code "52") (name "Net-(CN11USB-PadCC2)") (class "Default")
      (node (ref "CN11USB") (pin "CC2") (pinfunction "CC2_CC2") (pintype "bidirectional"))
      (node (ref "R15") (pin "2") (pinfunction "2_2") (pintype "passive"))
      (node (ref "R16") (pin "2") (pinfunction "2_2") (pintype "passive"))
    )
    (net (code "53") (name "Net-(LED4-BC)") (class "Default")
      (node (ref "LED3") (pin "C") (pinfunction "C_C") (pintype "passive"))
      (node (ref "LED4") (pin "3") (pinfunction "BC_3") (pintype "passive"))
      (node (ref "R12") (pin "2") (pinfunction "2_2") (pintype "passive"))
    )
    (net (code "54") (name "Net-(LED4-GC)") (class "Default")
      (node (ref "LED2") (pin "C") (pinfunction "C_C") (pintype "passive"))
      (node (ref "LED4") (pin "2") (pinfunction "GC_2") (pintype "passive"))
      (node (ref "R11") (pin "2") (pinfunction "2_2") (pintype "passive"))
    )
    (net (code "55") (name "Net-(LED4-RC)") (class "Default")
      (node (ref "LED1") (pin "C") (pinfunction "C_C") (pintype "passive"))
      (node (ref "LED4") (pin "1") (pinfunction "RC_1") (pintype "passive"))
      (node (ref "R10") (pin "2") (pinfunction "2_2") (pintype "passive"))
    )
    (net (code "56") (name "Net-(PWR-PadC)") (class "Default")
      (node (ref "PWR") (pin "C") (pinfunction "C_C") (pintype "passive"))
      (node (ref "R3") (pin "2") (pinfunction "2_2") (pintype "passive"))
    )
    (net (code "57") (name "Net-(R1-Pad2)") (class "Default")
      (node (ref "R1") (pin "2") (pinfunction "2_2") (pintype "passive"))
      (node (ref "T1") (pin "B") (pinfunction "B_B") (pintype "passive"))
    )
    (net (code "58") (name "Net-(R2-Pad2)") (class "Default")
      (node (ref "R2") (pin "2") (pinfunction "2_2") (pintype "passive"))
      (node (ref "T2") (pin "B") (pinfunction "B_B") (pintype "passive"))
    )
    (net (code "59") (name "Net-(R4-Pad2)") (class "Default")
      (node (ref "R4") (pin "2") (pinfunction "2_2") (pintype "passive"))
      (node (ref "TXD") (pin "C") (pinfunction "C_C") (pintype "passive"))
    )
    (net (code "60") (name "Net-(R5-Pad2)") (class "Default")
      (node (ref "R5") (pin "2") (pinfunction "2_2") (pintype "passive"))
      (node (ref "RXD") (pin "C") (pinfunction "C_C") (pintype "passive"))
    )
    (net (code "61") (name "unconnected-(CN4USB-ID-Pad4)") (class "Default")
      (node (ref "CN4USB") (pin "4") (pinfunction "ID_4") (pintype "passive"))
    )
    (net (code "62") (name "unconnected-(CN11USB-PadNC1)") (class "Default")
      (node (ref "CN11USB") (pin "NC1") (pinfunction "NC1_NC1") (pintype "bidirectional"))
    )
    (net (code "63") (name "unconnected-(CN11USB-PadNC2)") (class "Default")
      (node (ref "CN11USB") (pin "NC2") (pinfunction "NC2_NC2") (pintype "bidirectional"))
    )
    (net (code "64") (name "unconnected-(CN11USB-PadNC3)") (class "Default")
      (node (ref "CN11USB") (pin "NC3") (pinfunction "NC3_NC3") (pintype "bidirectional"))
    )
    (net (code "65") (name "unconnected-(CN11USB-PadNC4)") (class "Default")
      (node (ref "CN11USB") (pin "NC4") (pinfunction "NC4_NC4") (pintype "bidirectional"))
    )
    (net (code "66") (name "unconnected-(U3-CBUS0-Pad18)") (class "Default")
      (node (ref "U3") (pin "18") (pinfunction "CBUS0_18") (pintype "bidirectional"))
    )
    (net (code "67") (name "unconnected-(U3-CBUS3-Pad19)") (class "Default")
      (node (ref "U3") (pin "19") (pinfunction "CBUS3_19") (pintype "bidirectional"))
    )
    (net (code "68") (name "unconnected-(U3-CTS#-Pad9)") (class "Default")
      (node (ref "U3") (pin "9") (pinfunction "CTS#_9") (pintype "bidirectional"))
    )
    (net (code "69") (name "unconnected-(U3-DCD#-Pad8)") (class "Default")
      (node (ref "U3") (pin "8") (pinfunction "DCD#_8") (pintype "bidirectional"))
    )
    (net (code "70") (name "unconnected-(U3-DSR#-Pad7)") (class "Default")
      (node (ref "U3") (pin "7") (pinfunction "DSR#_7") (pintype "bidirectional"))
    )
    (net (code "71") (name "unconnected-(U3-RI#-Pad5)") (class "Default")
      (node (ref "U3") (pin "5") (pinfunction "RI#_5") (pintype "bidirectional"))
    )
  )
)
